# tl100-1-driver_sch-pcb.net
KiCad netlist of a schematic drawn in EAGLE
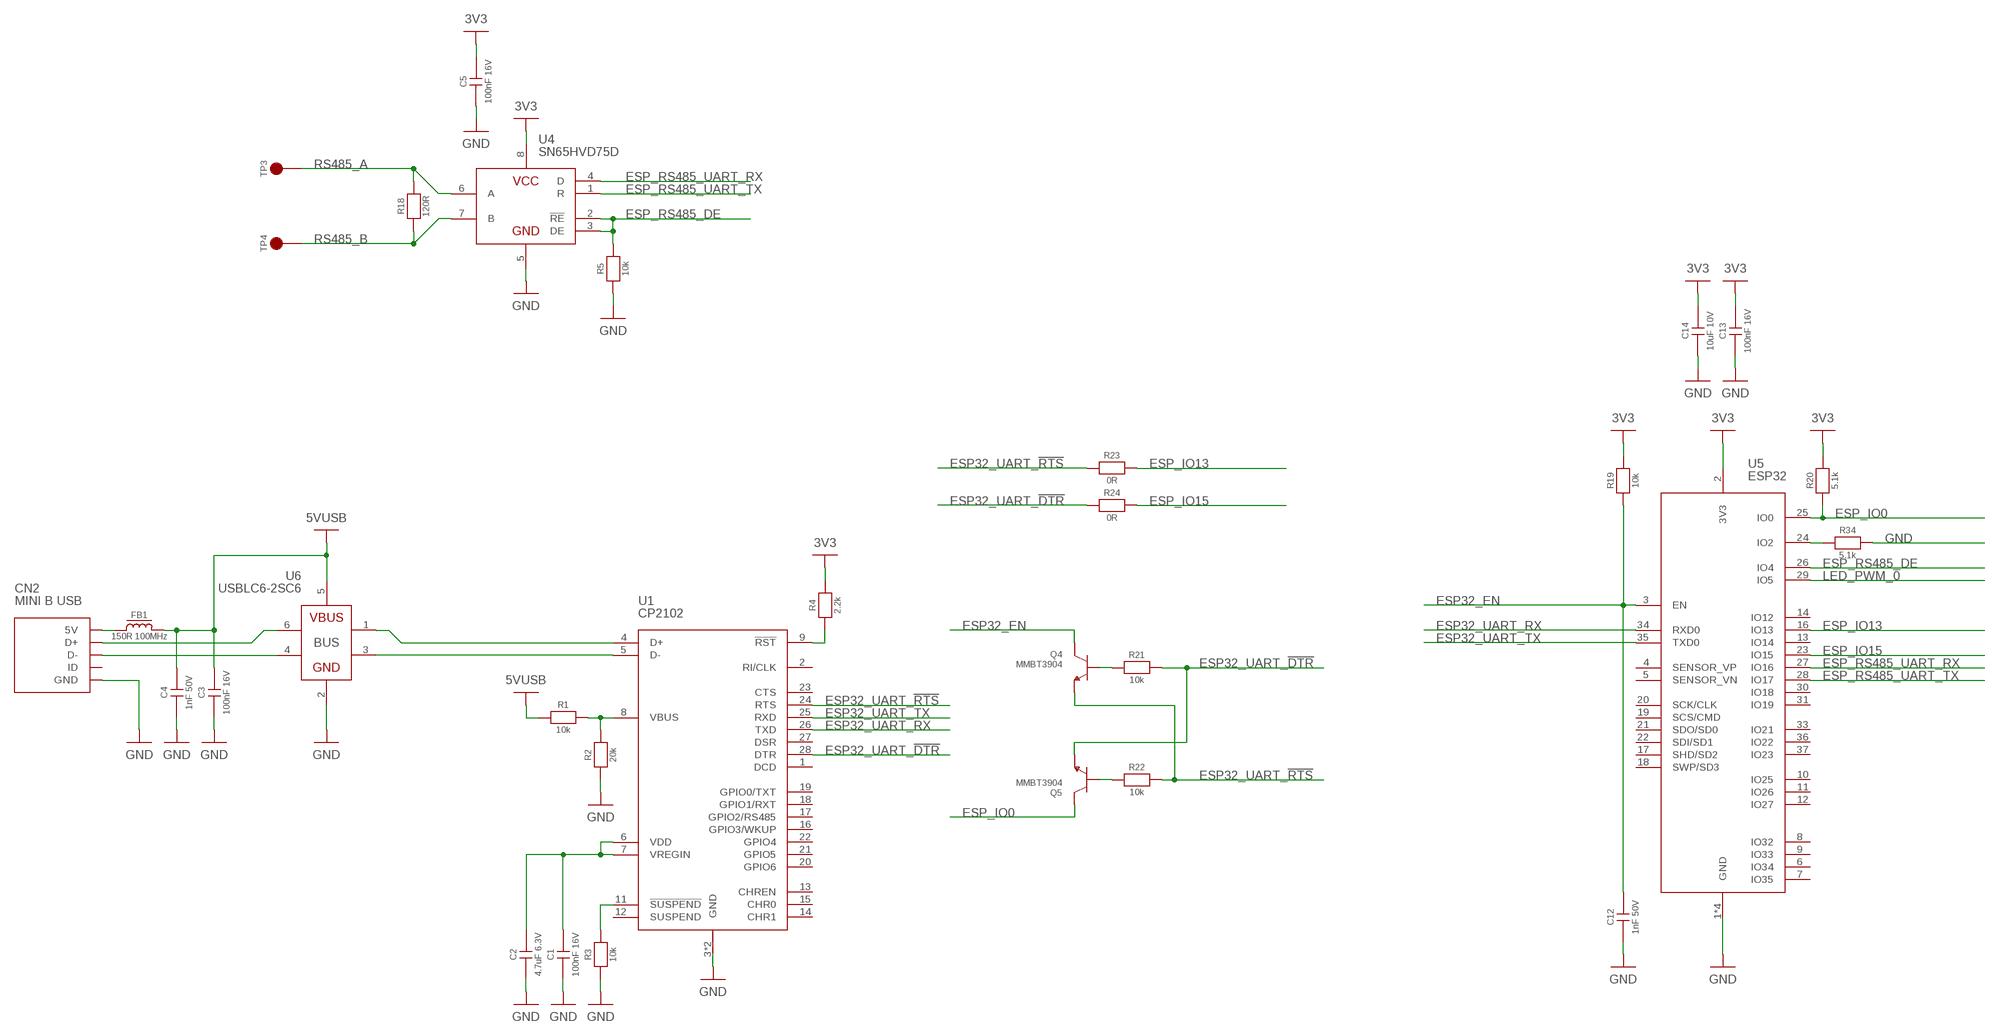
[diagram p0: schematic, sheet 1]
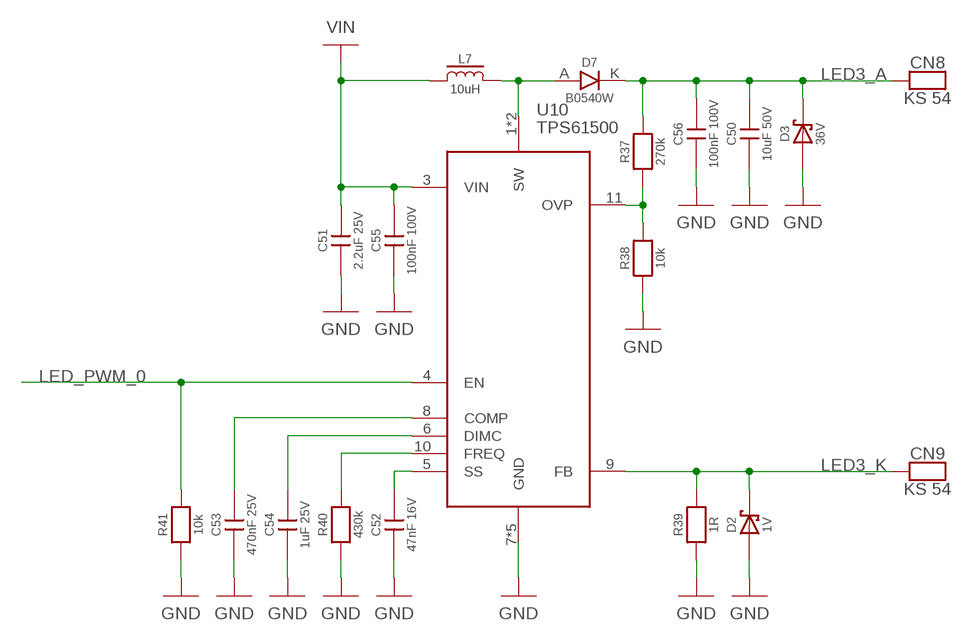
[diagram p1: schematic, sheet 2]
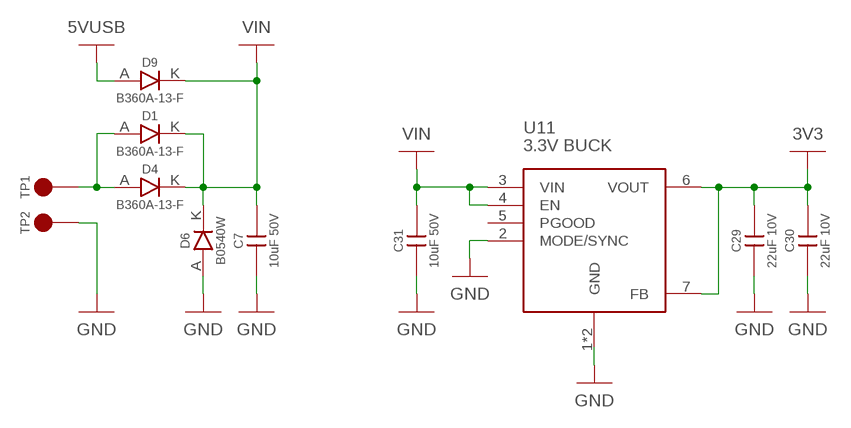
[diagram p2: schematic, sheet 3]
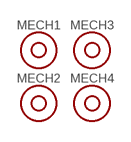
[diagram p3: schematic, sheet 4]

(export (version "E")
  (design (tool "Eeschema 10.0.6"))
  (components
    (comp (ref "C50")
      (value "10uF 50V")
      (footprint "eagle-import:1210")
      (libsource (lib "eagle-import") (part "C3225X7S1H106M250AB"))
    )
    (comp (ref "C51")
      (value "2.2uF 25V")
      (footprint "eagle-import:0603")
      (libsource (lib "eagle-import") (part "GRM188R61E225KA12D"))
    )
    (comp (ref "C52")
      (value "47nF 16V")
      (footprint "eagle-import:0603")
      (libsource (lib "eagle-import") (part "CL10B473KO8NNNC"))
    )
    (comp (ref "C53")
      (value "470nF 25V")
      (footprint "eagle-import:0603")
      (libsource (lib "eagle-import") (part "GRM188R71E474KA12D"))
    )
    (comp (ref "C54")
      (value "1uF 25V")
      (footprint "eagle-import:0603")
      (libsource (lib "eagle-import") (part "CL10A105KA8NNNC"))
    )
    (comp (ref "C55")
      (value "100nF 100V")
      (footprint "eagle-import:0603")
      (libsource (lib "eagle-import") (part "06031C104KAT2A"))
    )
    (comp (ref "C56")
      (value "100nF 100V")
      (footprint "eagle-import:0603")
      (libsource (lib "eagle-import") (part "06031C104KAT2A"))
    )
    (comp (ref "CN8")
      (value "KS 54")
      (footprint "eagle-import:KEYSTONE_54")
      (libsource (lib "eagle-import") (part "KEYSTONE_54"))
    )
    (comp (ref "CN9")
      (value "KS 54")
      (footprint "eagle-import:KEYSTONE_54")
      (libsource (lib "eagle-import") (part "KEYSTONE_54"))
    )
    (comp (ref "D2")
      (value "1V")
      (footprint "eagle-import:SC-79")
      (libsource (lib "eagle-import") (part "VESD01C1-02VHG3-08"))
    )
    (comp (ref "D3")
      (value "36V")
      (footprint "eagle-import:SOT23-3")
      (libsource (lib "eagle-import") (part "GSOT36-HE3-08"))
    )
    (comp (ref "D7")
      (value "B0540W")
      (footprint "eagle-import:SOD-123")
      (libsource (lib "eagle-import") (part "B0540W"))
    )
    (comp (ref "L7")
      (value "10uH")
      (footprint "eagle-import:SRN6045")
      (libsource (lib "eagle-import") (part "SRN6045-100M"))
    )
    (comp (ref "R37")
      (value "270k")
      (footprint "eagle-import:0603")
      (libsource (lib "eagle-import") (part "ERJ3EKF2703V"))
    )
    (comp (ref "R38")
      (value "10k")
      (footprint "eagle-import:0603")
      (libsource (lib "eagle-import") (part "ERJ3EKF1002V"))
    )
    (comp (ref "R39")
      (value "1R")
      (footprint "eagle-import:1206")
      (libsource (lib "eagle-import") (part "CRCW12061R00FKEA"))
    )
    (comp (ref "R40")
      (value "430k")
      (footprint "eagle-import:0603")
      (libsource (lib "eagle-import") (part "ERJ3EKF4303V"))
    )
    (comp (ref "R41")
      (value "10k")
      (footprint "eagle-import:0603")
      (libsource (lib "eagle-import") (part "ERJ3EKF1002V"))
    )
    (comp (ref "U10")
      (value "TPS61500")
      (footprint "eagle-import:HTSSOP14-4.5")
      (libsource (lib "eagle-import") (part "TPS61500"))
    )
    (comp (ref "MECH1")
      (value "6mm x 3mm")
      (footprint "eagle-import:MOUNTHOLE_6X3")
      (libsource (lib "eagle-import") (part "MOUNTHOLE"))
    )
    (comp (ref "MECH2")
      (value "6mm x 3mm")
      (footprint "eagle-import:MOUNTHOLE_6X3")
      (libsource (lib "eagle-import") (part "MOUNTHOLE"))
    )
    (comp (ref "MECH3")
      (value "6mm x 3mm")
      (footprint "eagle-import:MOUNTHOLE_6X3")
      (libsource (lib "eagle-import") (part "MOUNTHOLE"))
    )
    (comp (ref "MECH4")
      (value "6mm x 3mm")
      (footprint "eagle-import:MOUNTHOLE_6X3")
      (libsource (lib "eagle-import") (part "MOUNTHOLE"))
    )
    (comp (ref "C1")
      (value "100nF 16V")
      (footprint "eagle-import:0603")
      (libsource (lib "eagle-import") (part "CL10B104KO8WPNC"))
    )
    (comp (ref "C2")
      (value "4.7uF 6.3V")
      (footprint "eagle-import:0603")
      (libsource (lib "eagle-import") (part "GRM188R60J475ME19D"))
    )
    (comp (ref "C3")
      (value "100nF 16V")
      (footprint "eagle-import:0603")
      (libsource (lib "eagle-import") (part "CL10B104KO8WPNC"))
    )
    (comp (ref "C4")
      (value "1nF 50V")
      (footprint "eagle-import:0603")
      (libsource (lib "eagle-import") (part "CL10B102KB8NNNC"))
    )
    (comp (ref "C5")
      (value "100nF 16V")
      (footprint "eagle-import:0603")
      (libsource (lib "eagle-import") (part "CL10B104KO8WPNC"))
    )
    (comp (ref "C12")
      (value "1nF 50V")
      (footprint "eagle-import:0603")
      (libsource (lib "eagle-import") (part "CL10B102KB8NNNC"))
    )
    (comp (ref "C13")
      (value "100nF 16V")
      (footprint "eagle-import:0603")
      (libsource (lib "eagle-import") (part "CL10B104KO8WPNC"))
    )
    (comp (ref "C14")
      (value "10uF 10V")
      (footprint "eagle-import:0603")
      (libsource (lib "eagle-import") (part "GRM188R61A106KE69D"))
    )
    (comp (ref "CN2")
      (value "MINI B USB")
      (footprint "eagle-import:MUSB-05-S-B-SM-A")
      (libsource (lib "eagle-import") (part "MUSB-05-S-B-SM-A"))
    )
    (comp (ref "FB1")
      (value "150R 100MHz")
      (footprint "eagle-import:1206")
      (libsource (lib "eagle-import") (part "ILB1206ER151V"))
    )
    (comp (ref "Q4")
      (value "MMBT3904")
      (footprint "eagle-import:SOT23-3")
      (libsource (lib "eagle-import") (part "MMBT3904-7-F"))
    )
    (comp (ref "Q5")
      (value "MMBT3904")
      (footprint "eagle-import:SOT23-3")
      (libsource (lib "eagle-import") (part "MMBT3904-7-F"))
    )
    (comp (ref "R1")
      (value "10k")
      (footprint "eagle-import:0603")
      (libsource (lib "eagle-import") (part "ERJ3EKF1002V"))
    )
    (comp (ref "R2")
      (value "20k")
      (footprint "eagle-import:0603")
      (libsource (lib "eagle-import") (part "ERJ3EKF2002V"))
    )
    (comp (ref "R3")
      (value "10k")
      (footprint "eagle-import:0603")
      (libsource (lib "eagle-import") (part "ERJ3EKF1002V"))
    )
    (comp (ref "R4")
      (value "2.2k")
      (footprint "eagle-import:0603")
      (libsource (lib "eagle-import") (part "ERJ3EKF2201V"))
    )
    (comp (ref "R5")
      (value "10k")
      (footprint "eagle-import:0603")
      (libsource (lib "eagle-import") (part "ERJ3EKF1002V"))
    )
    (comp (ref "R18")
      (value "120R")
      (footprint "eagle-import:0603")
      (libsource (lib "eagle-import") (part "ERJ3EKF1200V"))
    )
    (comp (ref "R19")
      (value "10k")
      (footprint "eagle-import:0603")
      (libsource (lib "eagle-import") (part "ERJ3EKF1002V"))
    )
    (comp (ref "R20")
      (value "5.1k")
      (footprint "eagle-import:0603")
      (libsource (lib "eagle-import") (part "ERJ3EKF5101V"))
    )
    (comp (ref "R21")
      (value "10k")
      (footprint "eagle-import:0603")
      (libsource (lib "eagle-import") (part "ERJ3EKF1002V"))
    )
    (comp (ref "R22")
      (value "10k")
      (footprint "eagle-import:0603")
      (libsource (lib "eagle-import") (part "ERJ3EKF1002V"))
    )
    (comp (ref "R23")
      (value "0R")
      (footprint "eagle-import:0603")
      (libsource (lib "eagle-import") (part "CRCW06030000Z0EA"))
    )
    (comp (ref "R24")
      (value "0R")
      (footprint "eagle-import:0603")
      (libsource (lib "eagle-import") (part "CRCW06030000Z0EA"))
    )
    (comp (ref "R34")
      (value "5.1k")
      (footprint "eagle-import:0603")
      (libsource (lib "eagle-import") (part "ERJ3EKF5101V"))
    )
    (comp (ref "TP3")
      (value "2MM_TEST_POINT")
      (footprint "eagle-import:2MM_TEST_PAD")
      (libsource (lib "eagle-import") (part "2MM_TEST_POINT"))
    )
    (comp (ref "TP4")
      (value "2MM_TEST_POINT")
      (footprint "eagle-import:2MM_TEST_PAD")
      (libsource (lib "eagle-import") (part "2MM_TEST_POINT"))
    )
    (comp (ref "U1")
      (value "CP2102")
      (footprint "eagle-import:QFN28")
      (libsource (lib "eagle-import") (part "CP2102N-A01-GQFN28"))
    )
    (comp (ref "U4")
      (value "SN65HVD75D")
      (footprint "eagle-import:SO8")
      (libsource (lib "eagle-import") (part "SN65HVD75D"))
    )
    (comp (ref "U5")
      (value "ESP32")
      (footprint "eagle-import:ESP32-WROOM-32D")
      (libsource (lib "eagle-import") (part "ESP32-WROOM-32D"))
    )
    (comp (ref "U6")
      (value "USBLC6-2SC6")
      (footprint "eagle-import:SOT23-6")
      (libsource (lib "eagle-import") (part "USBLC6-2SC6"))
    )
    (comp (ref "C7")
      (value "10uF 50V")
      (footprint "eagle-import:1210")
      (libsource (lib "eagle-import") (part "C3225X7S1H106M250AB"))
    )
    (comp (ref "C29")
      (value "22uF 10V")
      (footprint "eagle-import:1206")
      (libsource (lib "eagle-import") (part "CL31B226MPHNNNE"))
    )
    (comp (ref "C30")
      (value "22uF 10V")
      (footprint "eagle-import:1206")
      (libsource (lib "eagle-import") (part "CL31B226MPHNNNE"))
    )
    (comp (ref "C31")
      (value "10uF 50V")
      (footprint "eagle-import:1210")
      (libsource (lib "eagle-import") (part "C3225X7S1H106M250AB"))
    )
    (comp (ref "D1")
      (value "B360A-13-F")
      (footprint "eagle-import:DO214AC")
      (libsource (lib "eagle-import") (part "B360A-13-F"))
    )
    (comp (ref "D4")
      (value "B360A-13-F")
      (footprint "eagle-import:DO214AC")
      (libsource (lib "eagle-import") (part "B360A-13-F"))
    )
    (comp (ref "D6")
      (value "B0540W")
      (footprint "eagle-import:SOD-123")
      (libsource (lib "eagle-import") (part "B0540W"))
    )
    (comp (ref "D9")
      (value "B360A-13-F")
      (footprint "eagle-import:DO214AC")
      (libsource (lib "eagle-import") (part "B360A-13-F"))
    )
    (comp (ref "TP1")
      (value "2MM_TEST_POINT")
      (footprint "eagle-import:2MM_TEST_PAD")
      (libsource (lib "eagle-import") (part "2MM_TEST_POINT"))
    )
    (comp (ref "TP2")
      (value "2MM_TEST_POINT")
      (footprint "eagle-import:2MM_TEST_PAD")
      (libsource (lib "eagle-import") (part "2MM_TEST_POINT"))
    )
    (comp (ref "U11")
      (value "3.3V BUCK")
      (footprint "eagle-import:TI_MICROSIP_10")
      (libsource (lib "eagle-import") (part "LMZM23600V3SILT"))
    )
  )
  (nets
    (net (code "1") (name "3V3") (class "Default")
      (node (ref "C13") (pin "2") (pinfunction "2_2") (pintype "bidirectional"))
      (node (ref "C14") (pin "2") (pinfunction "2_2") (pintype "bidirectional"))
      (node (ref "C29") (pin "2") (pinfunction "2_2") (pintype "bidirectional"))
      (node (ref "C30") (pin "2") (pinfunction "2_2") (pintype "bidirectional"))
      (node (ref "C5") (pin "2") (pinfunction "2_2") (pintype "bidirectional"))
      (node (ref "R19") (pin "2") (pinfunction "2_2") (pintype "bidirectional"))
      (node (ref "R20") (pin "2") (pinfunction "2_2") (pintype "bidirectional"))
      (node (ref "R4") (pin "2") (pinfunction "2_2") (pintype "bidirectional"))
      (node (ref "U11") (pin "6") (pinfunction "VOUT_6") (pintype "bidirectional"))
      (node (ref "U11") (pin "7") (pinfunction "FB_7") (pintype "bidirectional"))
      (node (ref "U4") (pin "8") (pinfunction "VCC_8") (pintype "bidirectional"))
      (node (ref "U5") (pin "2") (pinfunction "3V3_2") (pintype "bidirectional"))
    )
    (net (code "2") (name "5VUSB") (class "Default")
      (node (ref "C3") (pin "2") (pinfunction "2_2") (pintype "bidirectional"))
      (node (ref "C4") (pin "2") (pinfunction "2_2") (pintype "bidirectional"))
      (node (ref "D9") (pin "A") (pinfunction "A_A") (pintype "bidirectional"))
      (node (ref "FB1") (pin "2") (pinfunction "2_2") (pintype "bidirectional"))
      (node (ref "R1") (pin "1") (pinfunction "1_1") (pintype "bidirectional"))
      (node (ref "U6") (pin "5") (pinfunction "VBUS_5") (pintype "bidirectional"))
    )
    (net (code "3") (name "ESP32_EN") (class "Default")
      (node (ref "C12") (pin "2") (pinfunction "2_2") (pintype "bidirectional"))
      (node (ref "Q4") (pin "2") (pinfunction "C_2") (pintype "bidirectional"))
      (node (ref "R19") (pin "1") (pinfunction "1_1") (pintype "bidirectional"))
      (node (ref "U5") (pin "3") (pinfunction "EN_3") (pintype "bidirectional"))
    )
    (net (code "4") (name "ESP32_UART_RX") (class "Default")
      (node (ref "U1") (pin "26") (pinfunction "TXD_26") (pintype "bidirectional"))
      (node (ref "U5") (pin "34") (pinfunction "RXD0_34") (pintype "bidirectional"))
    )
    (net (code "5") (name "ESP32_UART_TX") (class "Default")
      (node (ref "U1") (pin "25") (pinfunction "RXD_25") (pintype "bidirectional"))
      (node (ref "U5") (pin "35") (pinfunction "TXD0_35") (pintype "bidirectional"))
    )
    (net (code "6") (name "ESP32_UART_~{DTR}") (class "Default")
      (node (ref "Q5") (pin "3") (pinfunction "E_3") (pintype "bidirectional"))
      (node (ref "R21") (pin "2") (pinfunction "2_2") (pintype "bidirectional"))
      (node (ref "R24") (pin "1") (pinfunction "1_1") (pintype "bidirectional"))
      (node (ref "U1") (pin "28") (pinfunction "DTR_28") (pintype "bidirectional"))
    )
    (net (code "7") (name "ESP32_UART_~{RTS}") (class "Default")
      (node (ref "Q4") (pin "3") (pinfunction "E_3") (pintype "bidirectional"))
      (node (ref "R22") (pin "2") (pinfunction "2_2") (pintype "bidirectional"))
      (node (ref "R23") (pin "1") (pinfunction "1_1") (pintype "bidirectional"))
      (node (ref "U1") (pin "24") (pinfunction "RTS_24") (pintype "bidirectional"))
    )
    (net (code "8") (name "ESP_IO0") (class "Default")
      (node (ref "Q5") (pin "2") (pinfunction "C_2") (pintype "bidirectional"))
      (node (ref "R20") (pin "1") (pinfunction "1_1") (pintype "bidirectional"))
      (node (ref "U5") (pin "25") (pinfunction "IO0_25") (pintype "bidirectional"))
    )
    (net (code "9") (name "ESP_IO13") (class "Default")
      (node (ref "R23") (pin "2") (pinfunction "2_2") (pintype "bidirectional"))
      (node (ref "U5") (pin "16") (pinfunction "IO13_16") (pintype "bidirectional"))
    )
    (net (code "10") (name "ESP_IO15") (class "Default")
      (node (ref "R24") (pin "2") (pinfunction "2_2") (pintype "bidirectional"))
      (node (ref "U5") (pin "23") (pinfunction "IO15_23") (pintype "bidirectional"))
    )
    (net (code "11") (name "ESP_RS485_DE") (class "Default")
      (node (ref "R5") (pin "2") (pinfunction "2_2") (pintype "bidirectional"))
      (node (ref "U4") (pin "2") (pinfunction "~{RE}_2") (pintype "bidirectional"))
      (node (ref "U4") (pin "3") (pinfunction "DE_3") (pintype "bidirectional"))
      (node (ref "U5") (pin "26") (pinfunction "IO4_26") (pintype "bidirectional"))
    )
    (net (code "12") (name "ESP_RS485_UART_RX") (class "Default")
      (node (ref "U4") (pin "4") (pinfunction "D_4") (pintype "bidirectional"))
      (node (ref "U5") (pin "27") (pinfunction "IO16_27") (pintype "bidirectional"))
    )
    (net (code "13") (name "ESP_RS485_UART_TX") (class "Default")
      (node (ref "U4") (pin "1") (pinfunction "R_1") (pintype "bidirectional"))
      (node (ref "U5") (pin "28") (pinfunction "IO17_28") (pintype "bidirectional"))
    )
    (net (code "14") (name "GND") (class "Default")
      (node (ref "C1") (pin "1") (pinfunction "1_1") (pintype "bidirectional"))
      (node (ref "C12") (pin "1") (pinfunction "1_1") (pintype "bidirectional"))
      (node (ref "C13") (pin "1") (pinfunction "1_1") (pintype "bidirectional"))
      (node (ref "C14") (pin "1") (pinfunction "1_1") (pintype "bidirectional"))
      (node (ref "C2") (pin "1") (pinfunction "1_1") (pintype "bidirectional"))
      (node (ref "C29") (pin "1") (pinfunction "1_1") (pintype "bidirectional"))
      (node (ref "C3") (pin "1") (pinfunction "1_1") (pintype "bidirectional"))
      (node (ref "C30") (pin "1") (pinfunction "1_1") (pintype "bidirectional"))
      (node (ref "C31") (pin "1") (pinfunction "1_1") (pintype "bidirectional"))
      (node (ref "C4") (pin "1") (pinfunction "1_1") (pintype "bidirectional"))
      (node (ref "C5") (pin "1") (pinfunction "1_1") (pintype "bidirectional"))
      (node (ref "C50") (pin "1") (pinfunction "1_1") (pintype "bidirectional"))
      (node (ref "C51") (pin "1") (pinfunction "1_1") (pintype "bidirectional"))
      (node (ref "C52") (pin "1") (pinfunction "1_1") (pintype "bidirectional"))
      (node (ref "C53") (pin "1") (pinfunction "1_1") (pintype "bidirectional"))
      (node (ref "C54") (pin "1") (pinfunction "1_1") (pintype "bidirectional"))
      (node (ref "C55") (pin "1") (pinfunction "1_1") (pintype "bidirectional"))
      (node (ref "C56") (pin "1") (pinfunction "1_1") (pintype "bidirectional"))
      (node (ref "C7") (pin "1") (pinfunction "1_1") (pintype "bidirectional"))
      (node (ref "CN2") (pin "GND") (pinfunction "GND_GND") (pintype "bidirectional"))
      (node (ref "CN2") (pin "SHIELD1") (pinfunction "GND_SHIELD1") (pintype "bidirectional"))
      (node (ref "CN2") (pin "SHIELD2") (pinfunction "GND_SHIELD2") (pintype "bidirectional"))
      (node (ref "CN2") (pin "SHIELD3") (pinfunction "GND_SHIELD3") (pintype "bidirectional"))
      (node (ref "CN2") (pin "SHIELD4") (pinfunction "GND_SHIELD4") (pintype "bidirectional"))
      (node (ref "D2") (pin "A") (pinfunction "A_A") (pintype "bidirectional"))
      (node (ref "D3") (pin "1") (pinfunction "A_1") (pintype "bidirectional"))
      (node (ref "D6") (pin "A") (pinfunction "A_A") (pintype "bidirectional"))
      (node (ref "R2") (pin "1") (pinfunction "1_1") (pintype "bidirectional"))
      (node (ref "R3") (pin "1") (pinfunction "1_1") (pintype "bidirectional"))
      (node (ref "R34") (pin "2") (pinfunction "2_2") (pintype "bidirectional"))
      (node (ref "R38") (pin "1") (pinfunction "1_1") (pintype "bidirectional"))
      (node (ref "R39") (pin "1") (pinfunction "1_1") (pintype "bidirectional"))
      (node (ref "R40") (pin "1") (pinfunction "1_1") (pintype "bidirectional"))
      (node (ref "R41") (pin "1") (pinfunction "1_1") (pintype "bidirectional"))
      (node (ref "R5") (pin "1") (pinfunction "1_1") (pintype "bidirectional"))
      (node (ref "TP2") (pin "1") (pinfunction "P$1_1") (pintype "bidirectional"))
      (node (ref "U1") (pin "29") (pinfunction "GND_29") (pintype "bidirectional"))
      (node (ref "U1") (pin "3") (pinfunction "GND_3") (pintype "bidirectional"))
      (node (ref "U10") (pin "12") (pinfunction "GND_12") (pintype "bidirectional"))
      (node (ref "U10") (pin "13") (pinfunction "GND_13") (pintype "bidirectional"))
      (node (ref "U10") (pin "14") (pinfunction "GND_14") (pintype "bidirectional"))
      (node (ref "U10") (pin "7") (pinfunction "GND_7") (pintype "bidirectional"))
      (node (ref "U10") (pin "PAD") (pinfunction "GND_PAD") (pintype "bidirectional"))
      (node (ref "U11") (pin "1") (pinfunction "GND_1") (pintype "bidirectional"))
      (node (ref "U11") (pin "2") (pinfunction "MODE/SYNC_2") (pintype "bidirectional"))
      (node (ref "U11") (pin "PAD") (pinfunction "GND_PAD") (pintype "bidirectional"))
      (node (ref "U4") (pin "5") (pinfunction "GND_5") (pintype "bidirectional"))
      (node (ref "U5") (pin "1") (pinfunction "GND_1") (pintype "bidirectional"))
      (node (ref "U5") (pin "15") (pinfunction "GND_15") (pintype "bidirectional"))
      (node (ref "U5") (pin "38") (pinfunction "GND_38") (pintype "bidirectional"))
      (node (ref "U5") (pin "39") (pinfunction "GND_39") (pintype "bidirectional"))
      (node (ref "U6") (pin "2") (pinfunction "GND_2") (pintype "bidirectional"))
    )
    (net (code "15") (name "LED3_A") (class "Default")
      (node (ref "C50") (pin "2") (pinfunction "2_2") (pintype "bidirectional"))
      (node (ref "C56") (pin "2") (pinfunction "2_2") (pintype "bidirectional"))
      (node (ref "CN8") (pin "P$1") (pinfunction "P$1_P$1") (pintype "bidirectional"))
      (node (ref "CN8") (pin "P$2") (pinfunction "P$1_P$2") (pintype "bidirectional"))
      (node (ref "CN8") (pin "P$3") (pinfunction "P$1_P$3") (pintype "bidirectional"))
      (node (ref "D3") (pin "2") (pinfunction "K_2") (pintype "bidirectional"))
      (node (ref "D7") (pin "K") (pinfunction "K_K") (pintype "bidirectional"))
      (node (ref "R37") (pin "2") (pinfunction "2_2") (pintype "bidirectional"))
    )
    (net (code "16") (name "LED3_K") (class "Default")
      (node (ref "CN9") (pin "P$1") (pinfunction "P$1_P$1") (pintype "bidirectional"))
      (node (ref "CN9") (pin "P$2") (pinfunction "P$1_P$2") (pintype "bidirectional"))
      (node (ref "CN9") (pin "P$3") (pinfunction "P$1_P$3") (pintype "bidirectional"))
      (node (ref "D2") (pin "K") (pinfunction "K_K") (pintype "bidirectional"))
      (node (ref "R39") (pin "2") (pinfunction "2_2") (pintype "bidirectional"))
      (node (ref "U10") (pin "9") (pinfunction "FB_9") (pintype "bidirectional"))
    )
    (net (code "17") (name "LED_PWM_0") (class "Default")
      (node (ref "R41") (pin "2") (pinfunction "2_2") (pintype "bidirectional"))
      (node (ref "U10") (pin "4") (pinfunction "EN_4") (pintype "bidirectional"))
      (node (ref "U5") (pin "29") (pinfunction "IO5_29") (pintype "bidirectional"))
    )
    (net (code "18") (name "Net-(CN2-5V)") (class "Default")
      (node (ref "CN2") (pin "VCC") (pinfunction "5V_VCC") (pintype "bidirectional"))
      (node (ref "FB1") (pin "1") (pinfunction "1_1") (pintype "bidirectional"))
    )
    (net (code "19") (name "Net-(D7-PadA)") (class "Default")
      (node (ref "D7") (pin "A") (pinfunction "A_A") (pintype "bidirectional"))
      (node (ref "L7") (pin "2") (pinfunction "2_2") (pintype "bidirectional"))
      (node (ref "U10") (pin "1") (pinfunction "SW_1") (pintype "bidirectional"))
      (node (ref "U10") (pin "2") (pinfunction "SW_2") (pintype "bidirectional"))
    )
    (net (code "20") (name "Net-(Q4-B)") (class "Default")
      (node (ref "Q4") (pin "1") (pinfunction "B_1") (pintype "bidirectional"))
      (node (ref "R21") (pin "1") (pinfunction "1_1") (pintype "bidirectional"))
    )
    (net (code "21") (name "Net-(Q5-B)") (class "Default")
      (node (ref "Q5") (pin "1") (pinfunction "B_1") (pintype "bidirectional"))
      (node (ref "R22") (pin "1") (pinfunction "1_1") (pintype "bidirectional"))
    )
    (net (code "22") (name "Net-(TP1-P$1)") (class "Default")
      (node (ref "D1") (pin "A") (pinfunction "A_A") (pintype "bidirectional"))
      (node (ref "D4") (pin "A") (pinfunction "A_A") (pintype "bidirectional"))
      (node (ref "TP1") (pin "1") (pinfunction "P$1_1") (pintype "bidirectional"))
    )
    (net (code "23") (name "Net-(U1-D+)") (class "Default")
      (node (ref "U1") (pin "4") (pinfunction "D+_4") (pintype "bidirectional"))
      (node (ref "U6") (pin "1") (pinfunction "D+_IN_1") (pintype "bidirectional"))
    )
    (net (code "24") (name "Net-(U1-D-)") (class "Default")
      (node (ref "U1") (pin "5") (pinfunction "D-_5") (pintype "bidirectional"))
      (node (ref "U6") (pin "3") (pinfunction "D-_IN_3") (pintype "bidirectional"))
    )
    (net (code "25") (name "Net-(U1-VBUS)") (class "Default")
      (node (ref "R1") (pin "2") (pinfunction "2_2") (pintype "bidirectional"))
      (node (ref "R2") (pin "2") (pinfunction "2_2") (pintype "bidirectional"))
      (node (ref "U1") (pin "8") (pinfunction "VBUS_8") (pintype "bidirectional"))
    )
    (net (code "26") (name "Net-(U1-VDD)") (class "Default")
      (node (ref "C1") (pin "2") (pinfunction "2_2") (pintype "bidirectional"))
      (node (ref "C2") (pin "2") (pinfunction "2_2") (pintype "bidirectional"))
      (node (ref "U1") (pin "6") (pinfunction "VDD_6") (pintype "bidirectional"))
      (node (ref "U1") (pin "7") (pinfunction "VREGIN_7") (pintype "bidirectional"))
    )
    (net (code "27") (name "Net-(U1-~{RST})") (class "Default")
      (node (ref "R4") (pin "1") (pinfunction "1_1") (pintype "bidirectional"))
      (node (ref "U1") (pin "9") (pinfunction "~{RST}_9") (pintype "bidirectional"))
    )
    (net (code "28") (name "Net-(U1-~{SUSPEND})") (class "Default")
      (node (ref "R3") (pin "2") (pinfunction "2_2") (pintype "bidirectional"))
      (node (ref "U1") (pin "11") (pinfunction "~{SUSPEND}_11") (pintype "bidirectional"))
    )
    (net (code "29") (name "Net-(U5-IO2)") (class "Default")
      (node (ref "R34") (pin "1") (pinfunction "1_1") (pintype "bidirectional"))
      (node (ref "U5") (pin "24") (pinfunction "IO2_24") (pintype "bidirectional"))
    )
    (net (code "30") (name "Net-(U6-D+_OUT)") (class "Default")
      (node (ref "CN2") (pin "D+") (pinfunction "D+_D+") (pintype "bidirectional"))
      (node (ref "U6") (pin "6") (pinfunction "D+_OUT_6") (pintype "bidirectional"))
    )
    (net (code "31") (name "Net-(U6-D-OUT)") (class "Default")
      (node (ref "CN2") (pin "D-") (pinfunction "D-_D-") (pintype "bidirectional"))
      (node (ref "U6") (pin "4") (pinfunction "D-OUT_4") (pintype "bidirectional"))
    )
    (net (code "32") (name "Net-(U10-COMP)") (class "Default")
      (node (ref "C53") (pin "2") (pinfunction "2_2") (pintype "bidirectional"))
      (node (ref "U10") (pin "8") (pinfunction "COMP_8") (pintype "bidirectional"))
    )
    (net (code "33") (name "Net-(U10-DIMC)") (class "Default")
      (node (ref "C54") (pin "2") (pinfunction "2_2") (pintype "bidirectional"))
      (node (ref "U10") (pin "6") (pinfunction "DIMC_6") (pintype "bidirectional"))
    )
    (net (code "34") (name "Net-(U10-FREQ)") (class "Default")
      (node (ref "R40") (pin "2") (pinfunction "2_2") (pintype "bidirectional"))
      (node (ref "U10") (pin "10") (pinfunction "FREQ_10") (pintype "bidirectional"))
    )
    (net (code "35") (name "Net-(U10-OVP)") (class "Default")
      (node (ref "R37") (pin "1") (pinfunction "1_1") (pintype "bidirectional"))
      (node (ref "R38") (pin "2") (pinfunction "2_2") (pintype "bidirectional"))
      (node (ref "U10") (pin "11") (pinfunction "OVP_11") (pintype "bidirectional"))
    )
    (net (code "36") (name "Net-(U10-SS)") (class "Default")
      (node (ref "C52") (pin "2") (pinfunction "2_2") (pintype "bidirectional"))
      (node (ref "U10") (pin "5") (pinfunction "SS_5") (pintype "bidirectional"))
    )
    (net (code "37") (name "RS485_A") (class "Default")
      (node (ref "R18") (pin "2") (pinfunction "2_2") (pintype "bidirectional"))
      (node (ref "TP3") (pin "1") (pinfunction "P$1_1") (pintype "bidirectional"))
      (node (ref "U4") (pin "6") (pinfunction "A_6") (pintype "bidirectional"))
    )
    (net (code "38") (name "RS485_B") (class "Default")
      (node (ref "R18") (pin "1") (pinfunction "1_1") (pintype "bidirectional"))
      (node (ref "TP4") (pin "1") (pinfunction "P$1_1") (pintype "bidirectional"))
      (node (ref "U4") (pin "7") (pinfunction "B_7") (pintype "bidirectional"))
    )
    (net (code "39") (name "VIN") (class "Default")
      (node (ref "C31") (pin "2") (pinfunction "2_2") (pintype "bidirectional"))
      (node (ref "C51") (pin "2") (pinfunction "2_2") (pintype "bidirectional"))
      (node (ref "C55") (pin "2") (pinfunction "2_2") (pintype "bidirectional"))
      (node (ref "C7") (pin "2") (pinfunction "2_2") (pintype "bidirectional"))
      (node (ref "D1") (pin "K") (pinfunction "K_K") (pintype "bidirectional"))
      (node (ref "D4") (pin "K") (pinfunction "K_K") (pintype "bidirectional"))
      (node (ref "D6") (pin "K") (pinfunction "K_K") (pintype "bidirectional"))
      (node (ref "D9") (pin "K") (pinfunction "K_K") (pintype "bidirectional"))
      (node (ref "L7") (pin "1") (pinfunction "1_1") (pintype "bidirectional"))
      (node (ref "U10") (pin "3") (pinfunction "VIN_3") (pintype "bidirectional"))
      (node (ref "U11") (pin "3") (pinfunction "VIN_3") (pintype "bidirectional"))
      (node (ref "U11") (pin "4") (pinfunction "EN_4") (pintype "bidirectional"))
    )
    (net (code "40") (name "unconnected-(CN2-PadID)") (class "Default")
      (node (ref "CN2") (pin "ID") (pinfunction "ID_ID") (pintype "bidirectional"))
    )
    (net (code "41") (name "unconnected-(U1-CHR0-Pad15)") (class "Default")
      (node (ref "U1") (pin "15") (pinfunction "CHR0_15") (pintype "bidirectional"))
    )
    (net (code "42") (name "unconnected-(U1-CHR1-Pad14)") (class "Default")
      (node (ref "U1") (pin "14") (pinfunction "CHR1_14") (pintype "bidirectional"))
    )
    (net (code "43") (name "unconnected-(U1-CHREN-Pad13)") (class "Default")
      (node (ref "U1") (pin "13") (pinfunction "CHREN_13") (pintype "bidirectional"))
    )
    (net (code "44") (name "unconnected-(U1-CTS-Pad23)") (class "Default")
      (node (ref "U1") (pin "23") (pinfunction "CTS_23") (pintype "bidirectional"))
    )
    (net (code "45") (name "unconnected-(U1-DCD-Pad1)") (class "Default")
      (node (ref "U1") (pin "1") (pinfunction "DCD_1") (pintype "bidirectional"))
    )
    (net (code "46") (name "unconnected-(U1-DSR-Pad27)") (class "Default")
      (node (ref "U1") (pin "27") (pinfunction "DSR_27") (pintype "bidirectional"))
    )
    (net (code "47") (name "unconnected-(U1-GPIO0{slash}TXT-Pad19)") (class "Default")
      (node (ref "U1") (pin "19") (pinfunction "GPIO0/TXT_19") (pintype "bidirectional"))
    )
    (net (code "48") (name "unconnected-(U1-GPIO1{slash}RXT-Pad18)") (class "Default")
      (node (ref "U1") (pin "18") (pinfunction "GPIO1/RXT_18") (pintype "bidirectional"))
    )
    (net (code "49") (name "unconnected-(U1-GPIO2{slash}RS485-Pad17)") (class "Default")
      (node (ref "U1") (pin "17") (pinfunction "GPIO2/RS485_17") (pintype "bidirectional"))
    )
    (net (code "50") (name "unconnected-(U1-GPIO3{slash}WKUP-Pad16)") (class "Default")
      (node (ref "U1") (pin "16") (pinfunction "GPIO3/WKUP_16") (pintype "bidirectional"))
    )
    (net (code "51") (name "unconnected-(U1-GPIO4-Pad22)") (class "Default")
      (node (ref "U1") (pin "22") (pinfunction "GPIO4_22") (pintype "bidirectional"))
    )
    (net (code "52") (name "unconnected-(U1-GPIO5-Pad21)") (class "Default")
      (node (ref "U1") (pin "21") (pinfunction "GPIO5_21") (pintype "bidirectional"))
    )
    (net (code "53") (name "unconnected-(U1-GPIO6-Pad20)") (class "Default")
      (node (ref "U1") (pin "20") (pinfunction "GPIO6_20") (pintype "bidirectional"))
    )
    (net (code "54") (name "unconnected-(U1-RI{slash}CLK-Pad2)") (class "Default")
      (node (ref "U1") (pin "2") (pinfunction "RI/CLK_2") (pintype "bidirectional"))
    )
    (net (code "55") (name "unconnected-(U1-SUSPEND-Pad12)") (class "Default")
      (node (ref "U1") (pin "12") (pinfunction "SUSPEND_12") (pintype "bidirectional"))
    )
    (net (code "56") (name "unconnected-(U5-IO12-Pad14)") (class "Default")
      (node (ref "U5") (pin "14") (pinfunction "IO12_14") (pintype "bidirectional"))
    )
    (net (code "57") (name "unconnected-(U5-IO14-Pad13)") (class "Default")
      (node (ref "U5") (pin "13") (pinfunction "IO14_13") (pintype "bidirectional"))
    )
    (net (code "58") (name "unconnected-(U5-IO18-Pad30)") (class "Default")
      (node (ref "U5") (pin "30") (pinfunction "IO18_30") (pintype "bidirectional"))
    )
    (net (code "59") (name "unconnected-(U5-IO19-Pad31)") (class "Default")
      (node (ref "U5") (pin "31") (pinfunction "IO19_31") (pintype "bidirectional"))
    )
    (net (code "60") (name "unconnected-(U5-IO21-Pad33)") (class "Default")
      (node (ref "U5") (pin "33") (pinfunction "IO21_33") (pintype "bidirectional"))
    )
    (net (code "61") (name "unconnected-(U5-IO22-Pad36)") (class "Default")
      (node (ref "U5") (pin "36") (pinfunction "IO22_36") (pintype "bidirectional"))
    )
    (net (code "62") (name "unconnected-(U5-IO23-Pad37)") (class "Default")
      (node (ref "U5") (pin "37") (pinfunction "IO23_37") (pintype "bidirectional"))
    )
    (net (code "63") (name "unconnected-(U5-IO25-Pad10)") (class "Default")
      (node (ref "U5") (pin "10") (pinfunction "IO25_10") (pintype "bidirectional"))
    )
    (net (code "64") (name "unconnected-(U5-IO26-Pad11)") (class "Default")
      (node (ref "U5") (pin "11") (pinfunction "IO26_11") (pintype "bidirectional"))
    )
    (net (code "65") (name "unconnected-(U5-IO27-Pad12)") (class "Default")
      (node (ref "U5") (pin "12") (pinfunction "IO27_12") (pintype "bidirectional"))
    )
    (net (code "66") (name "unconnected-(U5-IO32-Pad8)") (class "Default")
      (node (ref "U5") (pin "8") (pinfunction "IO32_8") (pintype "bidirectional"))
    )
    (net (code "67") (name "unconnected-(U5-IO33-Pad9)") (class "Default")
      (node (ref "U5") (pin "9") (pinfunction "IO33_9") (pintype "bidirectional"))
    )
    (net (code "68") (name "unconnected-(U5-IO34-Pad6)") (class "Default")
      (node (ref "U5") (pin "6") (pinfunction "IO34_6") (pintype "bidirectional"))
    )
    (net (code "69") (name "unconnected-(U5-IO35-Pad7)") (class "Default")
      (node (ref "U5") (pin "7") (pinfunction "IO35_7") (pintype "bidirectional"))
    )
    (net (code "70") (name "unconnected-(U5-SCK{slash}CLK-Pad20)") (class "Default")
      (node (ref "U5") (pin "20") (pinfunction "SCK/CLK_20") (pintype "bidirectional"))
    )
    (net (code "71") (name "unconnected-(U5-SCS{slash}CMD-Pad19)") (class "Default")
      (node (ref "U5") (pin "19") (pinfunction "SCS/CMD_19") (pintype "bidirectional"))
    )
    (net (code "72") (name "unconnected-(U5-SDI{slash}SD1-Pad22)") (class "Default")
      (node (ref "U5") (pin "22") (pinfunction "SDI/SD1_22") (pintype "bidirectional"))
    )
    (net (code "73") (name "unconnected-(U5-SDO{slash}SD0-Pad21)") (class "Default")
      (node (ref "U5") (pin "21") (pinfunction "SDO/SD0_21") (pintype "bidirectional"))
    )
    (net (code "74") (name "unconnected-(U5-SENSOR_VN-Pad5)") (class "Default")
      (node (ref "U5") (pin "5") (pinfunction "SENSOR_VN_5") (pintype "bidirectional"))
    )
    (net (code "75") (name "unconnected-(U5-SENSOR_VP-Pad4)") (class "Default")
      (node (ref "U5") (pin "4") (pinfunction "SENSOR_VP_4") (pintype "bidirectional"))
    )
    (net (code "76") (name "unconnected-(U5-SHD{slash}SD2-Pad17)") (class "Default")
      (node (ref "U5") (pin "17") (pinfunction "SHD/SD2_17") (pintype "bidirectional"))
    )
    (net (code "77") (name "unconnected-(U5-SWP{slash}SD3-Pad18)") (class "Default")
      (node (ref "U5") (pin "18") (pinfunction "SWP/SD3_18") (pintype "bidirectional"))
    )
    (net (code "78") (name "unconnected-(U11-PGOOD-Pad5)") (class "Default")
      (node (ref "U11") (pin "5") (pinfunction "PGOOD_5") (pintype "bidirectional"))
    )
  )
)
